# TC377TP_1.net
KiCad netlist of a schematic drawn in Altium Designer
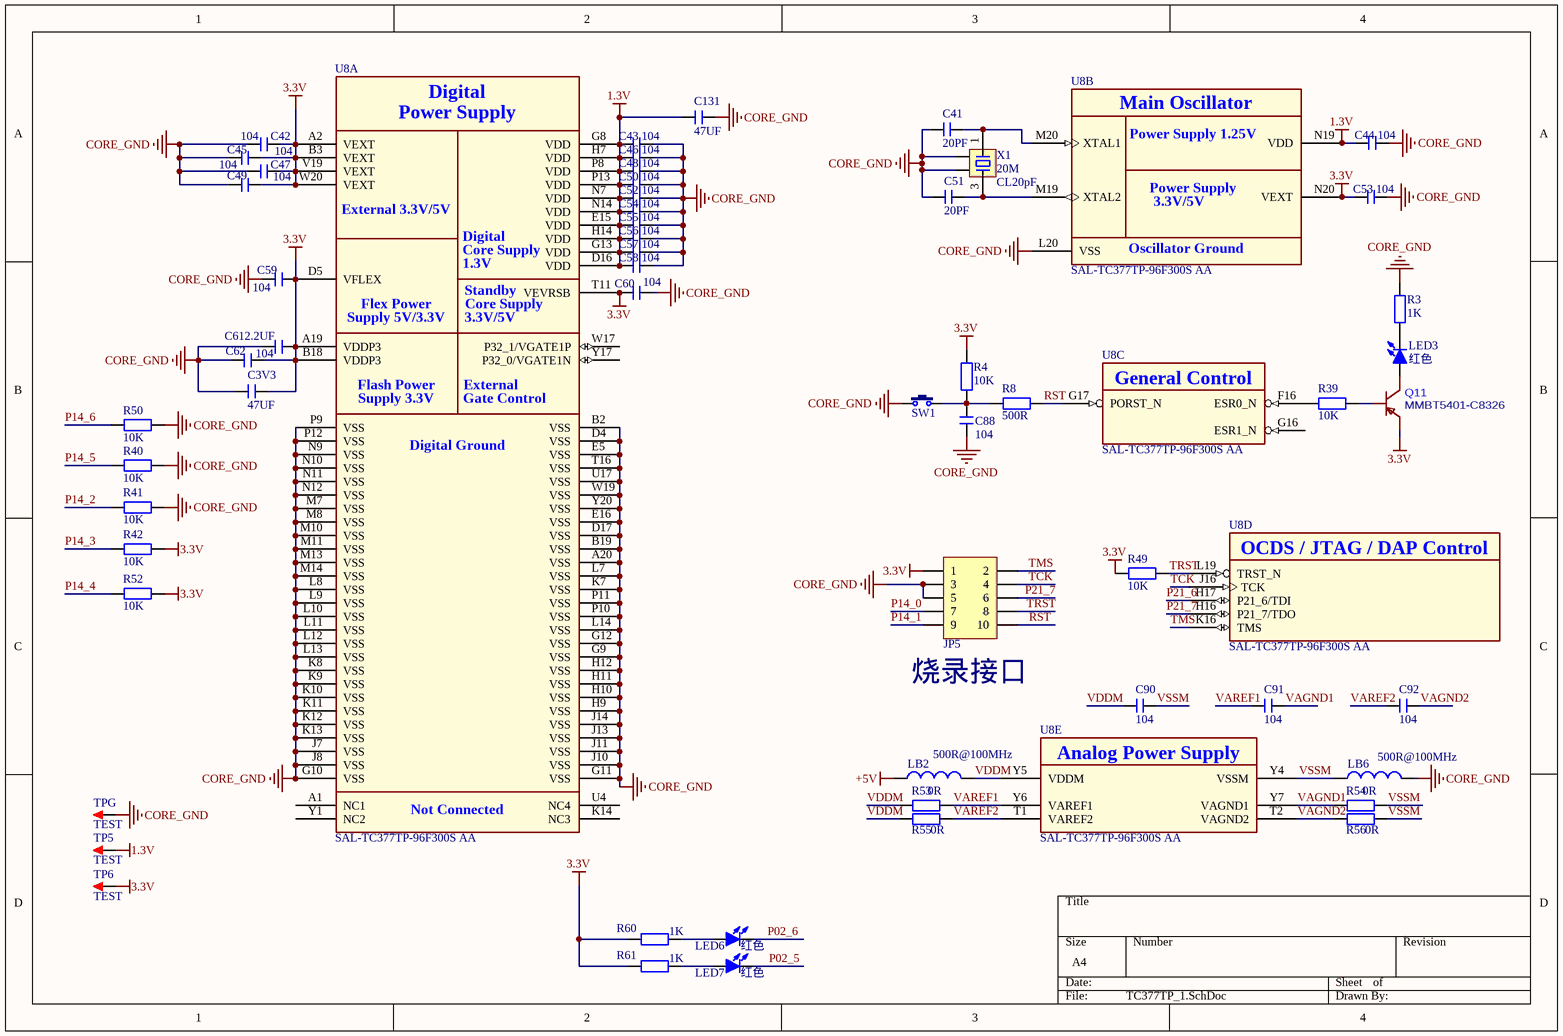
[diagram p0: TC377TP_1.SchDoc]

(export (version "E")
  (design (tool "Eeschema 10.0.6"))
  (components
    (comp (ref "C3V3")
      (value "47UF")
      (footprint "C 0805_L")
      (description "无极性贴片电容")
      (fields (field (name "版权归属") "源创客"))
      (libsource (lib "3.1   - 电阻-电容-电感") (part "C"))
    )
    (comp (ref "C41")
      (value "20PF")
      (footprint "C 0603_L")
      (description "无极性贴片电容")
      (fields (field (name "版权归属") "源创客"))
      (libsource (lib "3.1   - 电阻-电容-电感") (part "C"))
    )
    (comp (ref "C42")
      (value "104")
      (footprint "C 0603_L")
      (description "无极性贴片电容")
      (fields (field (name "版权归属") "源创客"))
      (libsource (lib "3.1   - 电阻-电容-电感") (part "C"))
    )
    (comp (ref "C43")
      (value "104")
      (footprint "C 0603_L")
      (description "无极性贴片电容")
      (fields (field (name "版权归属") "源创客"))
      (libsource (lib "3.1   - 电阻-电容-电感") (part "C"))
    )
    (comp (ref "C44")
      (value "104")
      (footprint "C 0603_L")
      (description "无极性贴片电容")
      (fields (field (name "版权归属") "源创客"))
      (libsource (lib "3.1   - 电阻-电容-电感") (part "C"))
    )
    (comp (ref "C45")
      (value "104")
      (footprint "C 0603_L")
      (description "无极性贴片电容")
      (fields (field (name "版权归属") "源创客"))
      (libsource (lib "3.1   - 电阻-电容-电感") (part "C"))
    )
    (comp (ref "C46")
      (value "104")
      (footprint "C 0603_L")
      (description "无极性贴片电容")
      (fields (field (name "版权归属") "源创客"))
      (libsource (lib "3.1   - 电阻-电容-电感") (part "C"))
    )
    (comp (ref "C47")
      (value "104")
      (footprint "C 0603_L")
      (description "无极性贴片电容")
      (fields (field (name "版权归属") "源创客"))
      (libsource (lib "3.1   - 电阻-电容-电感") (part "C"))
    )
    (comp (ref "C48")
      (value "104")
      (footprint "C 0603_L")
      (description "无极性贴片电容")
      (fields (field (name "版权归属") "源创客"))
      (libsource (lib "3.1   - 电阻-电容-电感") (part "C"))
    )
    (comp (ref "C49")
      (value "104")
      (footprint "C 0603_L")
      (description "无极性贴片电容")
      (fields (field (name "版权归属") "源创客"))
      (libsource (lib "3.1   - 电阻-电容-电感") (part "C"))
    )
    (comp (ref "C50")
      (value "104")
      (footprint "C 0603_L")
      (description "无极性贴片电容")
      (fields (field (name "版权归属") "源创客"))
      (libsource (lib "3.1   - 电阻-电容-电感") (part "C"))
    )
    (comp (ref "C51")
      (value "20PF")
      (footprint "C 0603_L")
      (description "无极性贴片电容")
      (fields (field (name "版权归属") "源创客"))
      (libsource (lib "3.1   - 电阻-电容-电感") (part "C"))
    )
    (comp (ref "C52")
      (value "104")
      (footprint "C 0603_L")
      (description "无极性贴片电容")
      (fields (field (name "版权归属") "源创客"))
      (libsource (lib "3.1   - 电阻-电容-电感") (part "C"))
    )
    (comp (ref "C53")
      (value "104")
      (footprint "C 0603_L")
      (description "无极性贴片电容")
      (fields (field (name "版权归属") "源创客"))
      (libsource (lib "3.1   - 电阻-电容-电感") (part "C"))
    )
    (comp (ref "C54")
      (value "104")
      (footprint "C 0603_L")
      (description "无极性贴片电容")
      (fields (field (name "版权归属") "源创客"))
      (libsource (lib "3.1   - 电阻-电容-电感") (part "C"))
    )
    (comp (ref "C55")
      (value "104")
      (footprint "C 0603_L")
      (description "无极性贴片电容")
      (fields (field (name "版权归属") "源创客"))
      (libsource (lib "3.1   - 电阻-电容-电感") (part "C"))
    )
    (comp (ref "C56")
      (value "104")
      (footprint "C 0603_L")
      (description "无极性贴片电容")
      (fields (field (name "版权归属") "源创客"))
      (libsource (lib "3.1   - 电阻-电容-电感") (part "C"))
    )
    (comp (ref "C57")
      (value "104")
      (footprint "C 0603_L")
      (description "无极性贴片电容")
      (fields (field (name "版权归属") "源创客"))
      (libsource (lib "3.1   - 电阻-电容-电感") (part "C"))
    )
    (comp (ref "C58")
      (value "104")
      (footprint "C 0603_L")
      (description "无极性贴片电容")
      (fields (field (name "版权归属") "源创客"))
      (libsource (lib "3.1   - 电阻-电容-电感") (part "C"))
    )
    (comp (ref "C59")
      (value "104")
      (footprint "C 0603_L")
      (description "无极性贴片电容")
      (fields (field (name "版权归属") "源创客"))
      (libsource (lib "3.1   - 电阻-电容-电感") (part "C"))
    )
    (comp (ref "C60")
      (value "104")
      (footprint "C 0603_L")
      (description "无极性贴片电容")
      (fields (field (name "版权归属") "源创客"))
      (libsource (lib "3.1   - 电阻-电容-电感") (part "C"))
    )
    (comp (ref "C61")
      (value "2.2UF")
      (footprint "C 0603_L")
      (description "无极性贴片电容")
      (fields (field (name "版权归属") "源创客"))
      (libsource (lib "3.1   - 电阻-电容-电感") (part "C"))
    )
    (comp (ref "C62")
      (value "104")
      (footprint "C 0603_L")
      (description "无极性贴片电容")
      (fields (field (name "版权归属") "源创客"))
      (libsource (lib "3.1   - 电阻-电容-电感") (part "C"))
    )
    (comp (ref "C88")
      (value "104")
      (footprint "C 0603_L")
      (description "无极性贴片电容")
      (fields (field (name "版权归属") "源创客"))
      (libsource (lib "3.1   - 电阻-电容-电感") (part "C"))
    )
    (comp (ref "C90")
      (value "104")
      (footprint "C 0603_L")
      (description "无极性贴片电容")
      (fields (field (name "版权归属") "源创客"))
      (libsource (lib "3.1   - 电阻-电容-电感") (part "C"))
    )
    (comp (ref "C91")
      (value "104")
      (footprint "C 0603_L")
      (description "无极性贴片电容")
      (fields (field (name "版权归属") "源创客"))
      (libsource (lib "3.1   - 电阻-电容-电感") (part "C"))
    )
    (comp (ref "C92")
      (value "104")
      (footprint "C 0603_L")
      (description "无极性贴片电容")
      (fields (field (name "版权归属") "源创客"))
      (libsource (lib "3.1   - 电阻-电容-电感") (part "C"))
    )
    (comp (ref "C131")
      (value "47UF")
      (footprint "C 0805_L")
      (description "无极性贴片电容")
      (fields (field (name "版权归属") "源创客"))
      (libsource (lib "3.1   - 电阻-电容-电感") (part "C"))
    )
    (comp (ref "JP5")
      (value "Header 5X2")
      (footprint "IDC2.54-LI-2x5P")
      (description "5*2P接插件")
      (fields (field (name "版权归属") "源创客"))
      (libsource (lib "4.6   - 接插件-脚距2.54") (part "Header 5X2"))
    )
    (comp (ref "LB2")
      (value "500R@100MHz")
      (footprint "FB 0603_L")
      (description "磁珠")
      (fields (field (name "版权归属") "源创客"))
      (libsource (lib "3.1   - 电阻-电容-电感") (part "LB"))
    )
    (comp (ref "LB6")
      (value "500R@100MHz")
      (footprint "FB 0603_L")
      (description "磁珠")
      (fields (field (name "版权归属") "源创客"))
      (libsource (lib "3.1   - 电阻-电容-电感") (part "LB"))
    )
    (comp (ref "LED3")
      (value "红色")
      (footprint "LED 0603Y")
      (description "贴片LED")
      (fields (field (name "版权归属") "源创客"))
      (libsource (lib "9.1   - LED") (part "LED-SMD"))
    )
    (comp (ref "LED6")
      (value "红色")
      (footprint "LED 0603Y")
      (description "贴片LED")
      (fields (field (name "版权归属") "源创客"))
      (libsource (lib "9.1   - LED") (part "LED-SMD"))
    )
    (comp (ref "LED7")
      (value "红色")
      (footprint "LED 0603Y")
      (description "贴片LED")
      (fields (field (name "版权归属") "源创客"))
      (libsource (lib "9.1   - LED") (part "LED-SMD"))
    )
    (comp (ref "Q11")
      (value "MMBT5401-C8326")
      (footprint "SOT23-3L")
      (libsource (lib "MMBT5401") (part "MMBT5401-C8326"))
    )
    (comp (ref "R3")
      (value "1K")
      (footprint "R 0603_L")
      (description "贴片电阻")
      (fields (field (name "版权归属") "源创客"))
      (libsource (lib "3.1   - 电阻-电容-电感") (part "R"))
    )
    (comp (ref "R4")
      (value "10K")
      (footprint "R 0603_L")
      (description "贴片电阻")
      (fields (field (name "版权归属") "源创客"))
      (libsource (lib "3.1   - 电阻-电容-电感") (part "R"))
    )
    (comp (ref "R8")
      (value "500R")
      (footprint "R 0603_L")
      (description "贴片电阻")
      (fields (field (name "版权归属") "源创客"))
      (libsource (lib "3.1   - 电阻-电容-电感") (part "R"))
    )
    (comp (ref "R39")
      (value "10K")
      (footprint "R 0603_L")
      (description "贴片电阻")
      (fields (field (name "版权归属") "源创客"))
      (libsource (lib "3.1   - 电阻-电容-电感") (part "R"))
    )
    (comp (ref "R40")
      (value "10K")
      (footprint "R 0603_L")
      (description "贴片电阻")
      (fields (field (name "版权归属") "源创客"))
      (libsource (lib "3.1   - 电阻-电容-电感") (part "R"))
    )
    (comp (ref "R41")
      (value "10K")
      (footprint "R 0603_L")
      (description "贴片电阻")
      (fields (field (name "版权归属") "源创客"))
      (libsource (lib "3.1   - 电阻-电容-电感") (part "R"))
    )
    (comp (ref "R42")
      (value "10K")
      (footprint "R 0603_L")
      (description "贴片电阻")
      (fields (field (name "版权归属") "源创客"))
      (libsource (lib "3.1   - 电阻-电容-电感") (part "R"))
    )
    (comp (ref "R49")
      (value "10K")
      (footprint "R 0805_L")
      (description "贴片电阻")
      (fields (field (name "版权归属") "源创客"))
      (libsource (lib "3.1   - 电阻-电容-电感") (part "R"))
    )
    (comp (ref "R50")
      (value "10K")
      (footprint "R 0603_L")
      (description "贴片电阻")
      (fields (field (name "版权归属") "源创客"))
      (libsource (lib "3.1   - 电阻-电容-电感") (part "R"))
    )
    (comp (ref "R52")
      (value "10K")
      (footprint "R 0603_L")
      (description "贴片电阻")
      (fields (field (name "版权归属") "源创客"))
      (libsource (lib "3.1   - 电阻-电容-电感") (part "R"))
    )
    (comp (ref "R53")
      (value "0R")
      (footprint "R 0603_L")
      (description "贴片电阻")
      (fields (field (name "版权归属") "源创客"))
      (libsource (lib "3.1   - 电阻-电容-电感") (part "R"))
    )
    (comp (ref "R54")
      (value "0R")
      (footprint "R 0603_L")
      (description "贴片电阻")
      (fields (field (name "版权归属") "源创客"))
      (libsource (lib "3.1   - 电阻-电容-电感") (part "R"))
    )
    (comp (ref "R55")
      (value "0R")
      (footprint "R 0603_L")
      (description "贴片电阻")
      (fields (field (name "版权归属") "源创客"))
      (libsource (lib "3.1   - 电阻-电容-电感") (part "R"))
    )
    (comp (ref "R56")
      (value "0R")
      (footprint "R 0603_L")
      (description "贴片电阻")
      (fields (field (name "版权归属") "源创客"))
      (libsource (lib "3.1   - 电阻-电容-电感") (part "R"))
    )
    (comp (ref "R60")
      (value "1K")
      (footprint "R 0603_L")
      (description "贴片电阻")
      (fields (field (name "版权归属") "源创客"))
      (libsource (lib "3.1   - 电阻-电容-电感") (part "R"))
    )
    (comp (ref "R61")
      (value "1K")
      (footprint "R 0603_L")
      (description "贴片电阻")
      (fields (field (name "版权归属") "源创客"))
      (libsource (lib "3.1   - 电阻-电容-电感") (part "R"))
    )
    (comp (ref "SW1")
      (value "3x6x5")
      (footprint "TSW SMD-3*6*2.5")
      (description "3x6轻触开关")
      (fields (field (name "版权归属") "源创客"))
      (libsource (lib "5.1   - 按键-开关") (part "TSW 3x6"))
    )
    (comp (ref "TP5")
      (value "TEST")
      (footprint "TEST 1.6")
      (description "测试点")
      (fields (field (name "版权归属") "源创客"))
      (libsource (lib "15.1 - 未分类器件") (part "TEST"))
    )
    (comp (ref "TP6")
      (value "TEST")
      (footprint "TEST 1.6")
      (description "测试点")
      (fields (field (name "版权归属") "源创客"))
      (libsource (lib "15.1 - 未分类器件") (part "TEST"))
    )
    (comp (ref "TPG")
      (value "TEST")
      (footprint "TEST 1.6")
      (description "测试点")
      (fields (field (name "版权归属") "源创客"))
      (libsource (lib "15.1 - 未分类器件") (part "TEST"))
    )
    (comp (ref "U8")
      (value "SAL-TC377TP-96F300S AA")
      (footprint "BGA292C80P20X20")
      (description "32-Bit Single-Chip Microcontroller")
      (fields (field (name "MANUFACTURER") "Infineon Technologies"))
      (libsource (lib "SAL-TC377TP-96F300S AA") (part "SAL-TC377TP-96F300S AA"))
    )
    (comp (ref "X1")
      (value "20M")
      (footprint "OSC 3225-4P")
      (description "4脚无源晶振")
      (fields (field (name "负载电容") "CL20pF") (field (name "版权归属") "源创客"))
      (libsource (lib "10.1 - 保险丝-晶振") (part "XTAL-4P"))
    )
  )
  (nets
    (net (code "1") (name "+5V") (class "Default")
      (node (ref "LB2") (pin "1") (pinfunction "1_1") (pintype "passive"))
    )
    (net (code "2") (name "/P02_5") (class "Default")
      (node (ref "LED7") (pin "2") (pinfunction "K_2") (pintype "passive"))
    )
    (net (code "3") (name "/P02_6") (class "Default")
      (node (ref "LED6") (pin "2") (pinfunction "K_2") (pintype "passive"))
    )
    (net (code "4") (name "/P14_0") (class "Default")
      (node (ref "JP5") (pin "7") (pinfunction "7_7") (pintype "passive"))
    )
    (net (code "5") (name "/P14_1") (class "Default")
      (node (ref "JP5") (pin "9") (pinfunction "9_9") (pintype "passive"))
    )
    (net (code "6") (name "/P14_2") (class "Default")
      (node (ref "R41") (pin "1") (pinfunction "1_1") (pintype "passive"))
    )
    (net (code "7") (name "/P14_3") (class "Default")
      (node (ref "R42") (pin "1") (pinfunction "1_1") (pintype "passive"))
    )
    (net (code "8") (name "/P14_4") (class "Default")
      (node (ref "R52") (pin "1") (pinfunction "1_1") (pintype "passive"))
    )
    (net (code "9") (name "/P14_5") (class "Default")
      (node (ref "R40") (pin "1") (pinfunction "1_1") (pintype "passive"))
    )
    (net (code "10") (name "/P14_6") (class "Default")
      (node (ref "R50") (pin "1") (pinfunction "1_1") (pintype "passive"))
    )
    (net (code "11") (name "/P21_6") (class "Default")
      (node (ref "U8") (pin "H17") (pinfunction "P21_6/TDI_H17") (pintype "bidirectional"))
    )
    (net (code "12") (name "/P21_7") (class "Default")
      (node (ref "JP5") (pin "6") (pinfunction "6_6") (pintype "passive"))
      (node (ref "U8") (pin "H16") (pinfunction "P21_7/TDO_H16") (pintype "bidirectional"))
    )
    (net (code "13") (name "/RST") (class "Default")
      (node (ref "JP5") (pin "10") (pinfunction "10_10") (pintype "passive"))
      (node (ref "R8") (pin "2") (pinfunction "2_2") (pintype "passive"))
      (node (ref "U8") (pin "G17") (pinfunction "PORST_N_G17") (pintype "input"))
    )
    (net (code "14") (name "/TCK") (class "Default")
      (node (ref "JP5") (pin "4") (pinfunction "4_4") (pintype "passive"))
      (node (ref "U8") (pin "J16") (pinfunction "TCK_J16") (pintype "input"))
    )
    (net (code "15") (name "/TMS") (class "Default")
      (node (ref "JP5") (pin "2") (pinfunction "2_2") (pintype "passive"))
      (node (ref "U8") (pin "K16") (pinfunction "TMS_K16") (pintype "bidirectional"))
    )
    (net (code "16") (name "/TRST") (class "Default")
      (node (ref "JP5") (pin "8") (pinfunction "8_8") (pintype "passive"))
      (node (ref "R49") (pin "1") (pinfunction "1_1") (pintype "passive"))
      (node (ref "U8") (pin "L19") (pinfunction "TRST_N_L19") (pintype "input"))
    )
    (net (code "17") (name "/VAGND1") (class "Default")
      (node (ref "C91") (pin "1") (pinfunction "1_1") (pintype "passive"))
      (node (ref "R54") (pin "1") (pinfunction "1_1") (pintype "passive"))
      (node (ref "U8") (pin "Y7") (pinfunction "VAGND1_Y7") (pintype "power_in"))
    )
    (net (code "18") (name "/VAGND2") (class "Default")
      (node (ref "C92") (pin "1") (pinfunction "1_1") (pintype "passive"))
      (node (ref "R56") (pin "1") (pinfunction "1_1") (pintype "passive"))
      (node (ref "U8") (pin "T2") (pinfunction "VAGND2_T2") (pintype "power_in"))
    )
    (net (code "19") (name "/VAREF1") (class "Default")
      (node (ref "C91") (pin "2") (pinfunction "2_2") (pintype "passive"))
      (node (ref "R53") (pin "2") (pinfunction "2_2") (pintype "passive"))
      (node (ref "U8") (pin "Y6") (pinfunction "VAREF1_Y6") (pintype "power_in"))
    )
    (net (code "20") (name "/VAREF2") (class "Default")
      (node (ref "C92") (pin "2") (pinfunction "2_2") (pintype "passive"))
      (node (ref "R55") (pin "2") (pinfunction "2_2") (pintype "passive"))
      (node (ref "U8") (pin "T1") (pinfunction "VAREF2_T1") (pintype "power_in"))
    )
    (net (code "21") (name "/VDDM") (class "Default")
      (node (ref "C90") (pin "2") (pinfunction "2_2") (pintype "passive"))
      (node (ref "LB2") (pin "2") (pinfunction "2_2") (pintype "passive"))
      (node (ref "R53") (pin "1") (pinfunction "1_1") (pintype "passive"))
      (node (ref "R55") (pin "1") (pinfunction "1_1") (pintype "passive"))
      (node (ref "U8") (pin "Y5") (pinfunction "VDDM_Y5") (pintype "power_in"))
    )
    (net (code "22") (name "/VSSM") (class "Default")
      (node (ref "C90") (pin "1") (pinfunction "1_1") (pintype "passive"))
      (node (ref "LB6") (pin "1") (pinfunction "1_1") (pintype "passive"))
      (node (ref "R54") (pin "2") (pinfunction "2_2") (pintype "passive"))
      (node (ref "R56") (pin "2") (pinfunction "2_2") (pintype "passive"))
      (node (ref "U8") (pin "Y4") (pinfunction "VSSM_Y4") (pintype "power_in"))
    )
    (net (code "23") (name "1.3V") (class "Default")
      (node (ref "C131") (pin "2") (pinfunction "2_2") (pintype "passive"))
      (node (ref "C43") (pin "2") (pinfunction "2_2") (pintype "passive"))
      (node (ref "C44") (pin "2") (pinfunction "2_2") (pintype "passive"))
      (node (ref "C46") (pin "2") (pinfunction "2_2") (pintype "passive"))
      (node (ref "C48") (pin "2") (pinfunction "2_2") (pintype "passive"))
      (node (ref "C50") (pin "2") (pinfunction "2_2") (pintype "passive"))
      (node (ref "C52") (pin "2") (pinfunction "2_2") (pintype "passive"))
      (node (ref "C54") (pin "2") (pinfunction "2_2") (pintype "passive"))
      (node (ref "C55") (pin "2") (pinfunction "2_2") (pintype "passive"))
      (node (ref "C56") (pin "2") (pinfunction "2_2") (pintype "passive"))
      (node (ref "C57") (pin "2") (pinfunction "2_2") (pintype "passive"))
      (node (ref "C58") (pin "2") (pinfunction "2_2") (pintype "passive"))
      (node (ref "TP5") (pin "1") (pinfunction "1_1") (pintype "passive"))
      (node (ref "U8") (pin "D16") (pinfunction "VDD_D16") (pintype "power_in"))
      (node (ref "U8") (pin "E15") (pinfunction "VDD_E15") (pintype "power_in"))
      (node (ref "U8") (pin "G13") (pinfunction "VDD_G13") (pintype "power_in"))
      (node (ref "U8") (pin "G8") (pinfunction "VDD_G8") (pintype "power_in"))
      (node (ref "U8") (pin "H14") (pinfunction "VDD_H14") (pintype "power_in"))
      (node (ref "U8") (pin "H7") (pinfunction "VDD_H7") (pintype "power_in"))
      (node (ref "U8") (pin "N14") (pinfunction "VDD_N14") (pintype "power_in"))
      (node (ref "U8") (pin "N19") (pinfunction "VDD_N19") (pintype "power_in"))
      (node (ref "U8") (pin "N7") (pinfunction "VDD_N7") (pintype "power_in"))
      (node (ref "U8") (pin "P13") (pinfunction "VDD_P13") (pintype "power_in"))
      (node (ref "U8") (pin "P8") (pinfunction "VDD_P8") (pintype "power_in"))
    )
    (net (code "24") (name "3.3V") (class "Default")
      (node (ref "C3V3") (pin "2") (pinfunction "2_2") (pintype "passive"))
      (node (ref "C42") (pin "1") (pinfunction "1_1") (pintype "passive"))
      (node (ref "C45") (pin "1") (pinfunction "1_1") (pintype "passive"))
      (node (ref "C47") (pin "1") (pinfunction "1_1") (pintype "passive"))
      (node (ref "C49") (pin "1") (pinfunction "1_1") (pintype "passive"))
      (node (ref "C53") (pin "2") (pinfunction "2_2") (pintype "passive"))
      (node (ref "C59") (pin "1") (pinfunction "1_1") (pintype "passive"))
      (node (ref "C60") (pin "2") (pinfunction "2_2") (pintype "passive"))
      (node (ref "C61") (pin "1") (pinfunction "1_1") (pintype "passive"))
      (node (ref "C62") (pin "1") (pinfunction "1_1") (pintype "passive"))
      (node (ref "JP5") (pin "1") (pinfunction "1_1") (pintype "passive"))
      (node (ref "Q11") (pin "2") (pinfunction "E_2") (pintype "passive"))
      (node (ref "R4") (pin "2") (pinfunction "2_2") (pintype "passive"))
      (node (ref "R42") (pin "2") (pinfunction "2_2") (pintype "passive"))
      (node (ref "R49") (pin "2") (pinfunction "2_2") (pintype "passive"))
      (node (ref "R52") (pin "2") (pinfunction "2_2") (pintype "passive"))
      (node (ref "R60") (pin "2") (pinfunction "2_2") (pintype "passive"))
      (node (ref "R61") (pin "2") (pinfunction "2_2") (pintype "passive"))
      (node (ref "TP6") (pin "1") (pinfunction "1_1") (pintype "passive"))
      (node (ref "U8") (pin "A19") (pinfunction "VDDP3_A19") (pintype "power_in"))
      (node (ref "U8") (pin "A2") (pinfunction "VEXT_A2") (pintype "power_in"))
      (node (ref "U8") (pin "B18") (pinfunction "VDDP3_B18") (pintype "power_in"))
      (node (ref "U8") (pin "B3") (pinfunction "VEXT_B3") (pintype "power_in"))
      (node (ref "U8") (pin "D5") (pinfunction "VFLEX_D5") (pintype "power_in"))
      (node (ref "U8") (pin "N20") (pinfunction "VEXT_N20") (pintype "power_in"))
      (node (ref "U8") (pin "T11") (pinfunction "VEVRSB_T11") (pintype "power_in"))
      (node (ref "U8") (pin "V19") (pinfunction "VEXT_V19") (pintype "power_in"))
      (node (ref "U8") (pin "W20") (pinfunction "VEXT_W20") (pintype "power_in"))
    )
    (net (code "25") (name "CORE_GND") (class "Default")
      (node (ref "C131") (pin "1") (pinfunction "1_1") (pintype "passive"))
      (node (ref "C3V3") (pin "1") (pinfunction "1_1") (pintype "passive"))
      (node (ref "C41") (pin "2") (pinfunction "2_2") (pintype "passive"))
      (node (ref "C42") (pin "2") (pinfunction "2_2") (pintype "passive"))
      (node (ref "C43") (pin "1") (pinfunction "1_1") (pintype "passive"))
      (node (ref "C44") (pin "1") (pinfunction "1_1") (pintype "passive"))
      (node (ref "C45") (pin "2") (pinfunction "2_2") (pintype "passive"))
      (node (ref "C46") (pin "1") (pinfunction "1_1") (pintype "passive"))
      (node (ref "C47") (pin "2") (pinfunction "2_2") (pintype "passive"))
      (node (ref "C48") (pin "1") (pinfunction "1_1") (pintype "passive"))
      (node (ref "C49") (pin "2") (pinfunction "2_2") (pintype "passive"))
      (node (ref "C50") (pin "1") (pinfunction "1_1") (pintype "passive"))
      (node (ref "C51") (pin "2") (pinfunction "2_2") (pintype "passive"))
      (node (ref "C52") (pin "1") (pinfunction "1_1") (pintype "passive"))
      (node (ref "C53") (pin "1") (pinfunction "1_1") (pintype "passive"))
      (node (ref "C54") (pin "1") (pinfunction "1_1") (pintype "passive"))
      (node (ref "C55") (pin "1") (pinfunction "1_1") (pintype "passive"))
      (node (ref "C56") (pin "1") (pinfunction "1_1") (pintype "passive"))
      (node (ref "C57") (pin "1") (pinfunction "1_1") (pintype "passive"))
      (node (ref "C58") (pin "1") (pinfunction "1_1") (pintype "passive"))
      (node (ref "C59") (pin "2") (pinfunction "2_2") (pintype "passive"))
      (node (ref "C60") (pin "1") (pinfunction "1_1") (pintype "passive"))
      (node (ref "C61") (pin "2") (pinfunction "2_2") (pintype "passive"))
      (node (ref "C62") (pin "2") (pinfunction "2_2") (pintype "passive"))
      (node (ref "C88") (pin "1") (pinfunction "1_1") (pintype "passive"))
      (node (ref "JP5") (pin "3") (pinfunction "3_3") (pintype "passive"))
      (node (ref "JP5") (pin "5") (pinfunction "5_5") (pintype "passive"))
      (node (ref "LB6") (pin "2") (pinfunction "2_2") (pintype "passive"))
      (node (ref "R3") (pin "1") (pinfunction "1_1") (pintype "passive"))
      (node (ref "R40") (pin "2") (pinfunction "2_2") (pintype "passive"))
      (node (ref "R41") (pin "2") (pinfunction "2_2") (pintype "passive"))
      (node (ref "R50") (pin "2") (pinfunction "2_2") (pintype "passive"))
      (node (ref "SW1") (pin "1") (pinfunction "1_1") (pintype "passive"))
      (node (ref "TPG") (pin "1") (pinfunction "1_1") (pintype "passive"))
      (node (ref "U8") (pin "A20") (pinfunction "VSS_A20") (pintype "power_in"))
      (node (ref "U8") (pin "B19") (pinfunction "VSS_B19") (pintype "power_in"))
      (node (ref "U8") (pin "B2") (pinfunction "VSS_B2") (pintype "power_in"))
      (node (ref "U8") (pin "D17") (pinfunction "VSS_D17") (pintype "power_in"))
      (node (ref "U8") (pin "D4") (pinfunction "VSS_D4") (pintype "power_in"))
      (node (ref "U8") (pin "E16") (pinfunction "VSS_E16") (pintype "power_in"))
      (node (ref "U8") (pin "E5") (pinfunction "VSS_E5") (pintype "power_in"))
      (node (ref "U8") (pin "G10") (pinfunction "VSS_G10") (pintype "power_in"))
      (node (ref "U8") (pin "G11") (pinfunction "VSS_G11") (pintype "power_in"))
      (node (ref "U8") (pin "G12") (pinfunction "VSS_G12") (pintype "power_in"))
      (node (ref "U8") (pin "G9") (pinfunction "VSS_G9") (pintype "power_in"))
      (node (ref "U8") (pin "H10") (pinfunction "VSS_H10") (pintype "power_in"))
      (node (ref "U8") (pin "H11") (pinfunction "VSS_H11") (pintype "power_in"))
      (node (ref "U8") (pin "H12") (pinfunction "VSS_H12") (pintype "power_in"))
      (node (ref "U8") (pin "H9") (pinfunction "VSS_H9") (pintype "power_in"))
      (node (ref "U8") (pin "J10") (pinfunction "VSS_J10") (pintype "power_in"))
      (node (ref "U8") (pin "J11") (pinfunction "VSS_J11") (pintype "power_in"))
      (node (ref "U8") (pin "J13") (pinfunction "VSS_J13") (pintype "power_in"))
      (node (ref "U8") (pin "J14") (pinfunction "VSS_J14") (pintype "power_in"))
      (node (ref "U8") (pin "J7") (pinfunction "VSS_J7") (pintype "power_in"))
      (node (ref "U8") (pin "J8") (pinfunction "VSS_J8") (pintype "power_in"))
      (node (ref "U8") (pin "K10") (pinfunction "VSS_K10") (pintype "power_in"))
      (node (ref "U8") (pin "K11") (pinfunction "VSS_K11") (pintype "power_in"))
      (node (ref "U8") (pin "K12") (pinfunction "VSS_K12") (pintype "power_in"))
      (node (ref "U8") (pin "K13") (pinfunction "VSS_K13") (pintype "power_in"))
      (node (ref "U8") (pin "K7") (pinfunction "VSS_K7") (pintype "power_in"))
      (node (ref "U8") (pin "K8") (pinfunction "VSS_K8") (pintype "power_in"))
      (node (ref "U8") (pin "K9") (pinfunction "VSS_K9") (pintype "power_in"))
      (node (ref "U8") (pin "L10") (pinfunction "VSS_L10") (pintype "power_in"))
      (node (ref "U8") (pin "L11") (pinfunction "VSS_L11") (pintype "power_in"))
      (node (ref "U8") (pin "L12") (pinfunction "VSS_L12") (pintype "power_in"))
      (node (ref "U8") (pin "L13") (pinfunction "VSS_L13") (pintype "power_in"))
      (node (ref "U8") (pin "L14") (pinfunction "VSS_L14") (pintype "power_in"))
      (node (ref "U8") (pin "L20") (pinfunction "VSS_L20") (pintype "power_in"))
      (node (ref "U8") (pin "L7") (pinfunction "VSS_L7") (pintype "power_in"))
      (node (ref "U8") (pin "L8") (pinfunction "VSS_L8") (pintype "power_in"))
      (node (ref "U8") (pin "L9") (pinfunction "VSS_L9") (pintype "power_in"))
      (node (ref "U8") (pin "M10") (pinfunction "VSS_M10") (pintype "power_in"))
      (node (ref "U8") (pin "M11") (pinfunction "VSS_M11") (pintype "power_in"))
      (node (ref "U8") (pin "M13") (pinfunction "VSS_M13") (pintype "power_in"))
      (node (ref "U8") (pin "M14") (pinfunction "VSS_M14") (pintype "power_in"))
      (node (ref "U8") (pin "M7") (pinfunction "VSS_M7") (pintype "power_in"))
      (node (ref "U8") (pin "M8") (pinfunction "VSS_M8") (pintype "power_in"))
      (node (ref "U8") (pin "N10") (pinfunction "VSS_N10") (pintype "power_in"))
      (node (ref "U8") (pin "N11") (pinfunction "VSS_N11") (pintype "power_in"))
      (node (ref "U8") (pin "N12") (pinfunction "VSS_N12") (pintype "power_in"))
      (node (ref "U8") (pin "N9") (pinfunction "VSS_N9") (pintype "power_in"))
      (node (ref "U8") (pin "P10") (pinfunction "VSS_P10") (pintype "power_in"))
      (node (ref "U8") (pin "P11") (pinfunction "VSS_P11") (pintype "power_in"))
      (node (ref "U8") (pin "P12") (pinfunction "VSS_P12") (pintype "power_in"))
      (node (ref "U8") (pin "P9") (pinfunction "VSS_P9") (pintype "power_in"))
      (node (ref "U8") (pin "T16") (pinfunction "VSS_T16") (pintype "power_in"))
      (node (ref "U8") (pin "U17") (pinfunction "VSS_U17") (pintype "power_in"))
      (node (ref "U8") (pin "W19") (pinfunction "VSS_W19") (pintype "power_in"))
      (node (ref "U8") (pin "Y20") (pinfunction "VSS_Y20") (pintype "power_in"))
      (node (ref "X1") (pin "2") (pinfunction "2_2") (pintype "passive"))
      (node (ref "X1") (pin "4") (pinfunction "4_4") (pintype "passive"))
    )
    (net (code "26") (name "Net-(C88-Pad2)") (class "Default")
      (node (ref "C88") (pin "2") (pinfunction "2_2") (pintype "passive"))
      (node (ref "R4") (pin "1") (pinfunction "1_1") (pintype "passive"))
      (node (ref "R8") (pin "1") (pinfunction "1_1") (pintype "passive"))
      (node (ref "SW1") (pin "2") (pinfunction "2_2") (pintype "passive"))
    )
    (net (code "27") (name "Net-(LED3-A)") (class "Default")
      (node (ref "LED3") (pin "1") (pinfunction "A_1") (pintype "passive"))
      (node (ref "Q11") (pin "3") (pinfunction "C_3") (pintype "passive"))
    )
    (net (code "28") (name "Net-(LED3-K)") (class "Default")
      (node (ref "LED3") (pin "2") (pinfunction "K_2") (pintype "passive"))
      (node (ref "R3") (pin "2") (pinfunction "2_2") (pintype "passive"))
    )
    (net (code "29") (name "Net-(LED6-A)") (class "Default")
      (node (ref "LED6") (pin "1") (pinfunction "A_1") (pintype "passive"))
      (node (ref "R60") (pin "1") (pinfunction "1_1") (pintype "passive"))
    )
    (net (code "30") (name "Net-(LED7-A)") (class "Default")
      (node (ref "LED7") (pin "1") (pinfunction "A_1") (pintype "passive"))
      (node (ref "R61") (pin "1") (pinfunction "1_1") (pintype "passive"))
    )
    (net (code "31") (name "Net-(Q11-B)") (class "Default")
      (node (ref "Q11") (pin "1") (pinfunction "B_1") (pintype "passive"))
      (node (ref "R39") (pin "1") (pinfunction "1_1") (pintype "passive"))
    )
    (net (code "32") (name "Net-(U8B-XTAL1)") (class "Default")
      (node (ref "C41") (pin "1") (pinfunction "1_1") (pintype "passive"))
      (node (ref "U8") (pin "M20") (pinfunction "XTAL1_M20") (pintype "input"))
      (node (ref "X1") (pin "1") (pinfunction "1_1") (pintype "passive"))
    )
    (net (code "33") (name "Net-(U8B-XTAL2)") (class "Default")
      (node (ref "C51") (pin "1") (pinfunction "1_1") (pintype "passive"))
      (node (ref "U8") (pin "M19") (pinfunction "XTAL2_M19") (pintype "output"))
      (node (ref "X1") (pin "3") (pinfunction "3_3") (pintype "passive"))
    )
    (net (code "34") (name "Net-(U8C-ESR0_N)") (class "Default")
      (node (ref "R39") (pin "2") (pinfunction "2_2") (pintype "passive"))
      (node (ref "U8") (pin "F16") (pinfunction "ESR0_N_F16") (pintype "input"))
    )
    (net (code "35") (name "unconnected-(U8A-NC1-PadA1)") (class "Default")
      (node (ref "U8") (pin "A1") (pinfunction "NC1_A1") (pintype "passive"))
    )
    (net (code "36") (name "unconnected-(U8A-NC2-PadY1)") (class "Default")
      (node (ref "U8") (pin "Y1") (pinfunction "NC2_Y1") (pintype "passive"))
    )
    (net (code "37") (name "unconnected-(U8A-NC3-PadK14)") (class "Default")
      (node (ref "U8") (pin "K14") (pinfunction "NC3_K14") (pintype "passive"))
    )
    (net (code "38") (name "unconnected-(U8A-NC4-PadU4)") (class "Default")
      (node (ref "U8") (pin "U4") (pinfunction "NC4_U4") (pintype "passive"))
    )
    (net (code "39") (name "unconnected-(U8A-P32_0{slash}VGATE1N-PadY17)") (class "Default")
      (node (ref "U8") (pin "Y17") (pinfunction "P32_0/VGATE1N_Y17") (pintype "bidirectional"))
    )
    (net (code "40") (name "unconnected-(U8A-P32_1{slash}VGATE1P-PadW17)") (class "Default")
      (node (ref "U8") (pin "W17") (pinfunction "P32_1/VGATE1P_W17") (pintype "bidirectional"))
    )
    (net (code "41") (name "unconnected-(U8C-ESR1_N-PadG16)") (class "Default")
      (node (ref "U8") (pin "G16") (pinfunction "ESR1_N_G16") (pintype "input"))
    )
  )
)
